# main.net
KiCad netlist of a schematic drawn in Altium Designer
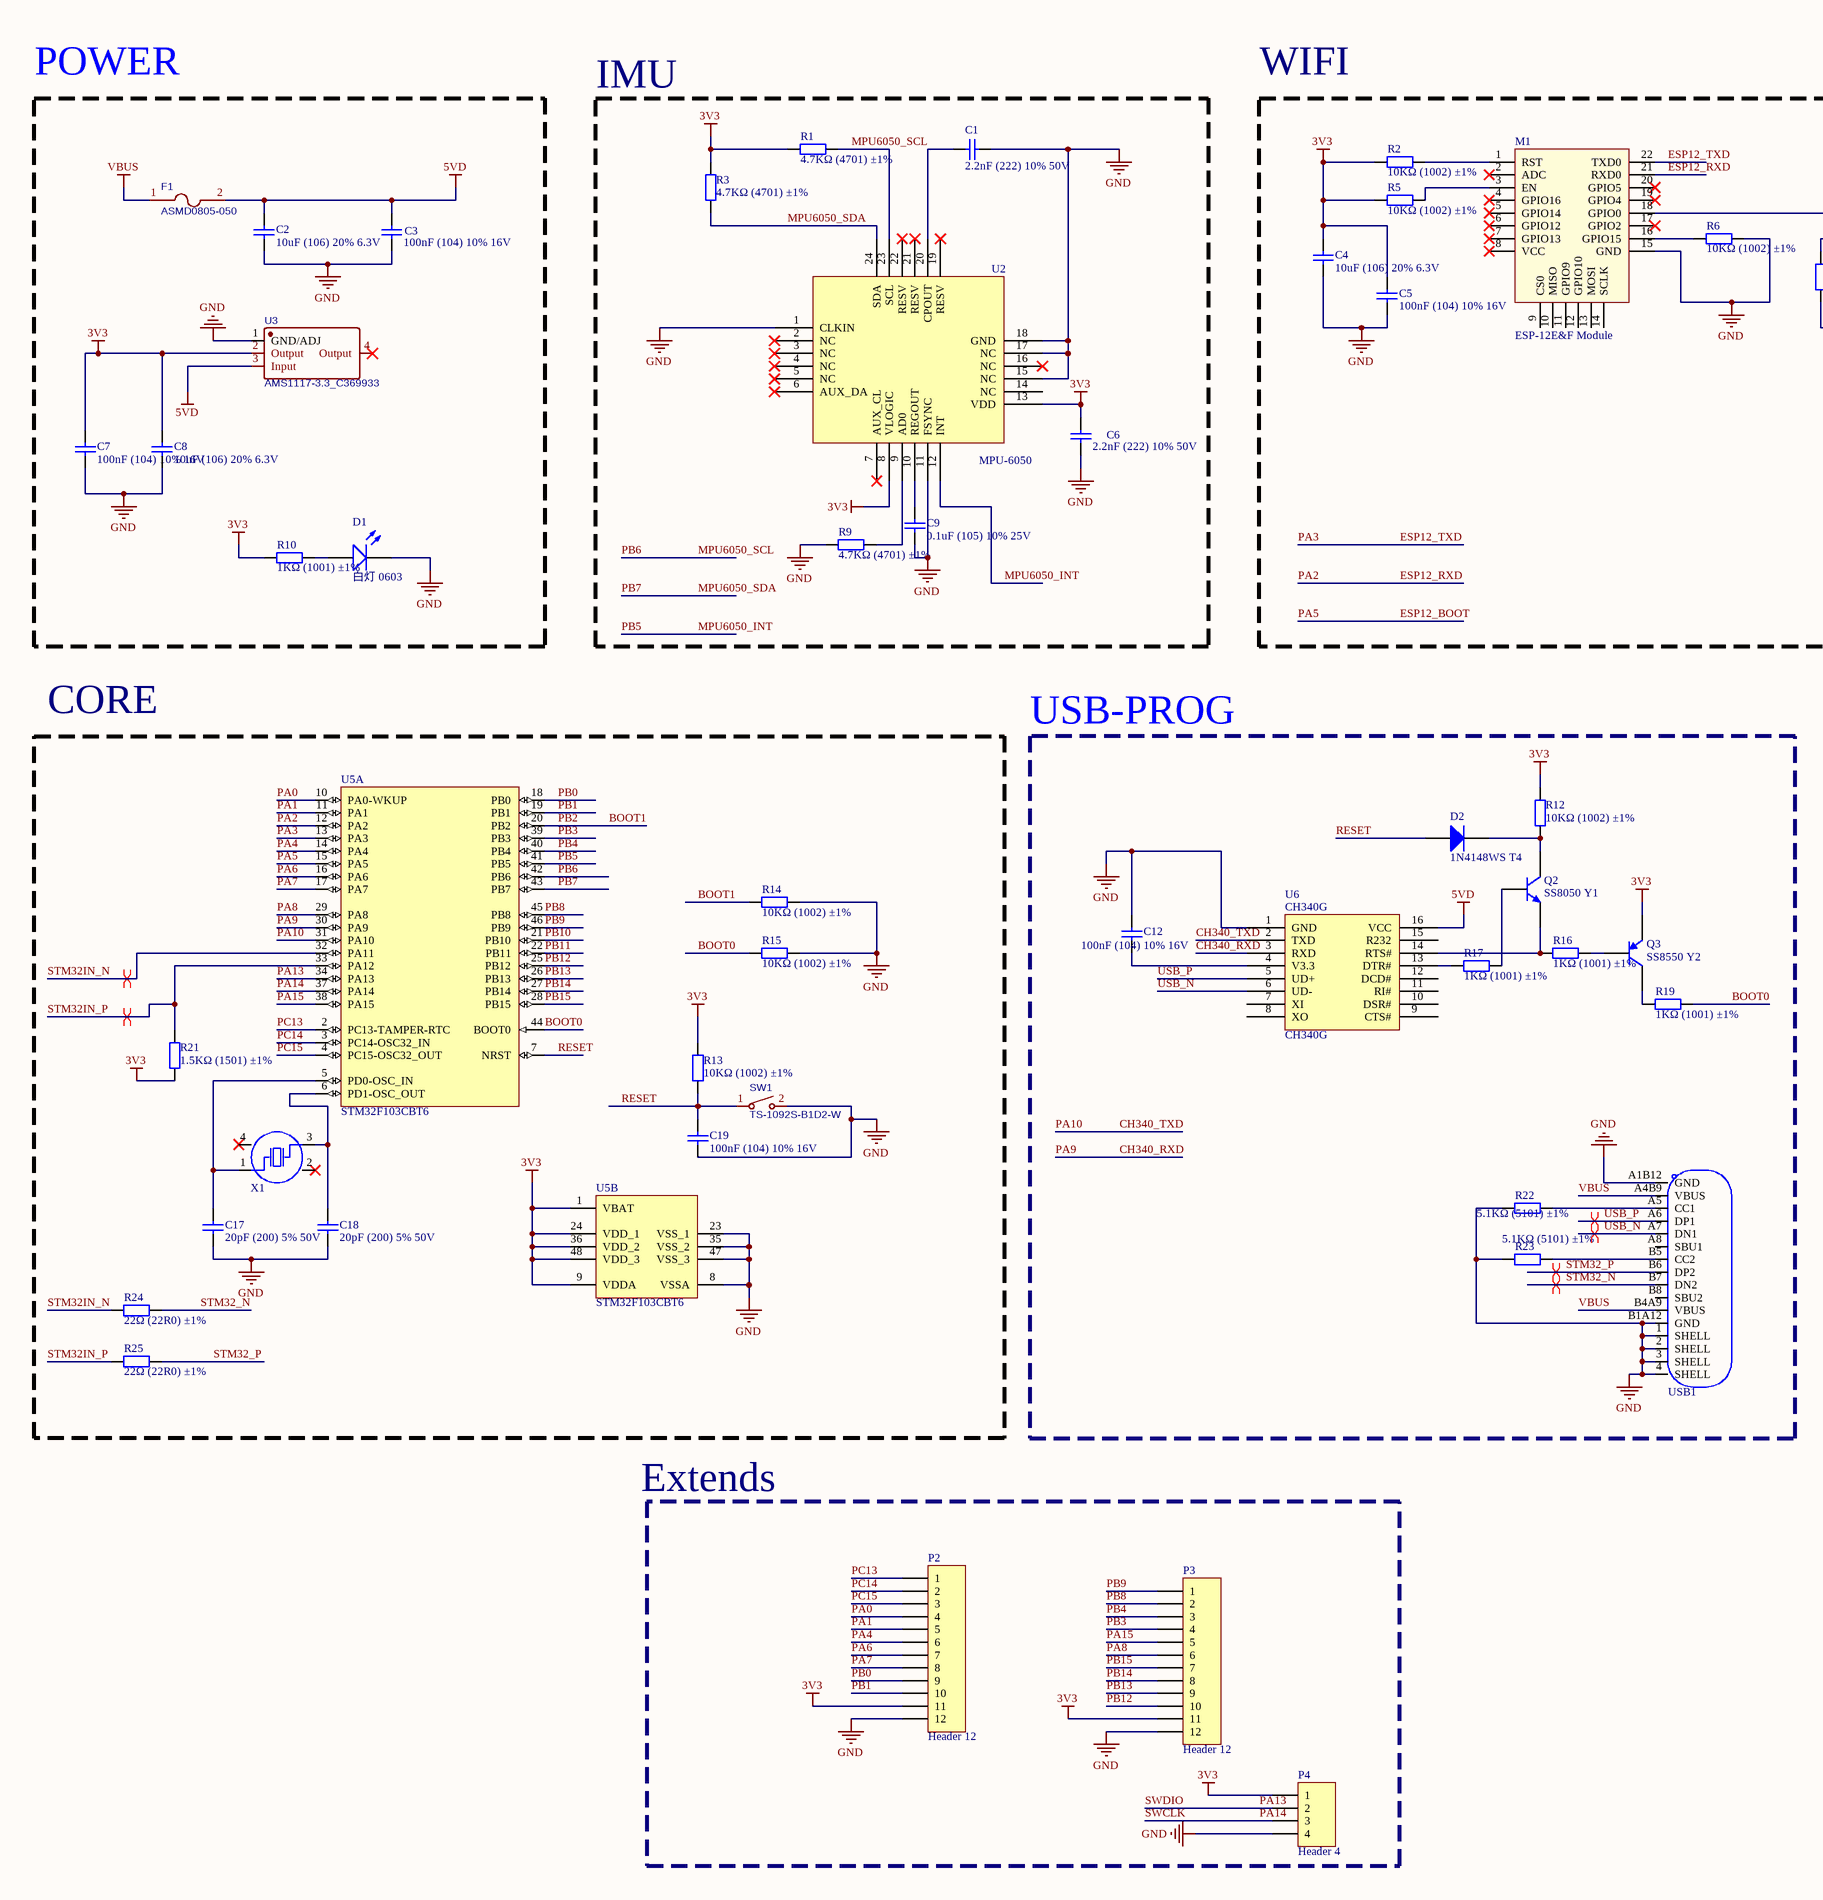
[diagram p0: main.SchDoc, left]
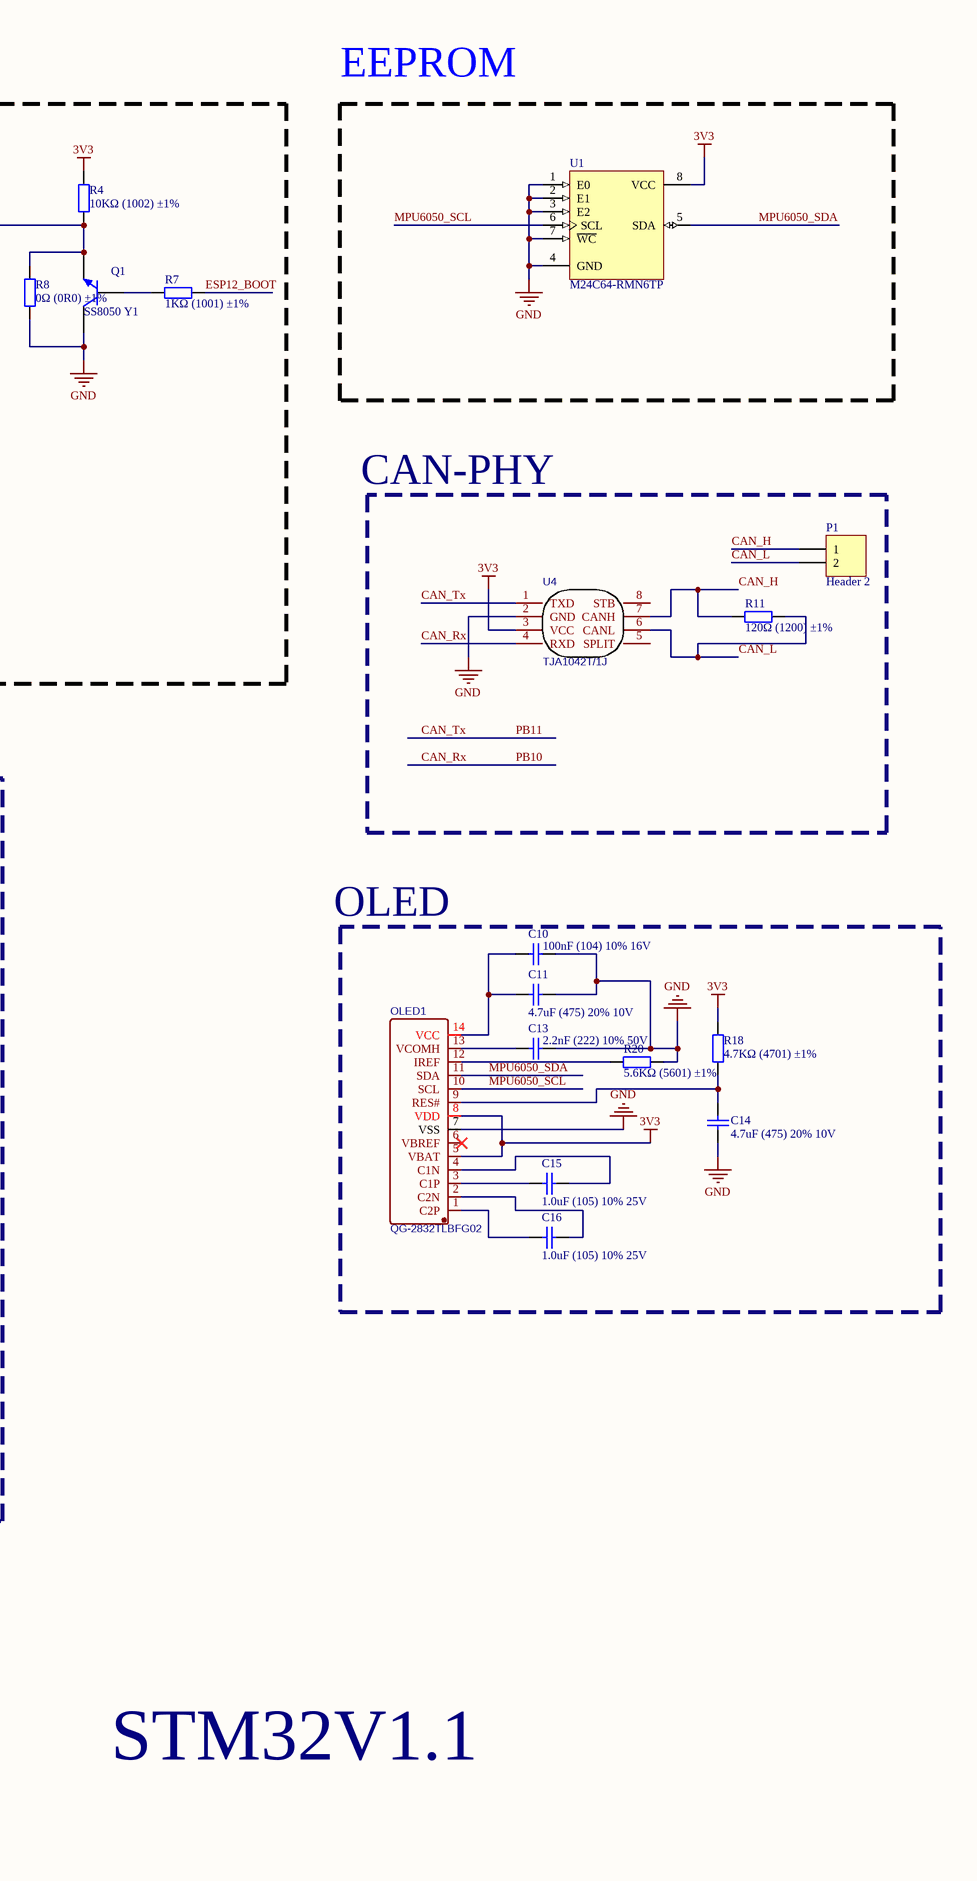
[diagram p1: main.SchDoc, right]

(export (version "E")
  (design (tool "Eeschema 10.0.6"))
  (components
    (comp (ref "C1")
      (value "2.2nF (222) 10% 50V")
      (footprint "0402_C")
      (description "贴片电容")
      (libsource (lib "Miscellaneous Devices LC") (part "0402 2.2nF (222) 10% 50V"))
    )
    (comp (ref "C2")
      (value "10uF (106) 20% 6.3V")
      (footprint "0402_C")
      (description "贴片电容")
      (libsource (lib "Cap") (part "0402 10uF (106) 20% 6.3V"))
    )
    (comp (ref "C3")
      (value "100nF (104) 10% 16V")
      (footprint "0402_C")
      (description "贴片电容")
      (libsource (lib "Cap") (part "0402 100nF (104) 10% 16V"))
    )
    (comp (ref "C4")
      (value "10uF (106) 20% 6.3V")
      (footprint "0402_C")
      (description "贴片电容")
      (libsource (lib "Miscellaneous Devices LC") (part "0402 10uF (106) 20% 6.3V"))
    )
    (comp (ref "C5")
      (value "100nF (104) 10% 16V")
      (footprint "0402_C")
      (description "贴片电容")
      (libsource (lib "Miscellaneous Devices LC") (part "0402 100nF (104) 10% 16V"))
    )
    (comp (ref "C6")
      (value "2.2nF (222) 10% 50V")
      (footprint "0402_C")
      (description "贴片电容")
      (libsource (lib "Miscellaneous Devices LC") (part "0402 2.2nF (222) 10% 50V"))
    )
    (comp (ref "C7")
      (value "100nF (104) 10% 16V")
      (footprint "0402_C")
      (description "贴片电容")
      (libsource (lib "Miscellaneous Devices LC") (part "0402 100nF (104) 10% 16V"))
    )
    (comp (ref "C8")
      (value "10uF (106) 20% 6.3V")
      (footprint "0402_C")
      (description "贴片电容")
      (libsource (lib "Miscellaneous Devices LC") (part "0402 10uF (106) 20% 6.3V"))
    )
    (comp (ref "C9")
      (value "0.1uF (105) 10% 25V")
      (footprint "0402_C")
      (description "贴片电容")
      (libsource (lib "Miscellaneous Devices LC") (part "0402 1.0uF (105) 10% 25V"))
    )
    (comp (ref "C10")
      (value "100nF (104) 10% 16V")
      (footprint "0402_C")
      (description "贴片电容")
      (libsource (lib "Miscellaneous Devices LC") (part "0402 100nF (104) 10% 16V"))
    )
    (comp (ref "C11")
      (value "4.7uF (475) 20% 10V")
      (footprint "0402_C")
      (description "贴片电容")
      (libsource (lib "Miscellaneous Devices LC") (part "0402 4.7uF (475) 20% 10V"))
    )
    (comp (ref "C12")
      (value "100nF (104) 10% 16V")
      (footprint "0402_C")
      (description "贴片电容")
      (libsource (lib "Miscellaneous Devices LC") (part "0402 100nF (104) 10% 16V"))
    )
    (comp (ref "C13")
      (value "2.2nF (222) 10% 50V")
      (footprint "0402_C")
      (description "贴片电容")
      (libsource (lib "Miscellaneous Devices LC") (part "0402 2.2nF (222) 10% 50V"))
    )
    (comp (ref "C14")
      (value "4.7uF (475) 20% 10V")
      (footprint "0402_C")
      (description "贴片电容")
      (libsource (lib "Miscellaneous Devices LC") (part "0402 4.7uF (475) 20% 10V"))
    )
    (comp (ref "C15")
      (value "1.0uF (105) 10% 25V")
      (footprint "0402_C")
      (description "贴片电容")
      (libsource (lib "Miscellaneous Devices LC") (part "0402 1.0uF (105) 10% 25V"))
    )
    (comp (ref "C16")
      (value "1.0uF (105) 10% 25V")
      (footprint "0402_C")
      (description "贴片电容")
      (libsource (lib "Miscellaneous Devices LC") (part "0402 1.0uF (105) 10% 25V"))
    )
    (comp (ref "C17")
      (value "20pF (200) 5% 50V")
      (footprint "0402_C")
      (description "贴片电容")
      (libsource (lib "Miscellaneous Devices LC") (part "0402 20pF (200) 5% 50V"))
    )
    (comp (ref "C18")
      (value "20pF (200) 5% 50V")
      (footprint "0402_C")
      (description "贴片电容")
      (libsource (lib "Miscellaneous Devices LC") (part "0402 20pF (200) 5% 50V"))
    )
    (comp (ref "C19")
      (value "100nF (104) 10% 16V")
      (footprint "0402_C")
      (description "贴片电容")
      (libsource (lib "Miscellaneous Devices LC") (part "0402 100nF (104) 10% 16V"))
    )
    (comp (ref "D1")
      (value "白灯 0603")
      (footprint "0603_LED_S1")
      (description "发光二极管")
      (libsource (lib "Miscellaneous Devices LC") (part "0603 白灯"))
    )
    (comp (ref "D2")
      (value "1N4148WS T4")
      (footprint "SOD-323_L1.8-W1.3-LS2.5-RD")
      (description "二极管")
      (libsource (lib "Miscellaneous Devices LC") (part "SOD-323 1N4148WS T4"))
    )
    (comp (ref "F1")
      (value "ASMD0805-050")
      (footprint "ASMD0805")
      (fields (field (name "BOM_SUPPLIER PART") "C135329") (field (name "CONTRIBUTOR") "LCSC"))
      (libsource (lib "mysch") (part "ASMD0805-050"))
    )
    (comp (ref "M1")
      (value "ESP-12E&F Module")
      (footprint "ESP-12E&F Module")
      (libsource (lib "smartclock") (part "ESP-12E&F Module"))
    )
    (comp (ref "OLED1")
      (value "QG-2832TLBFG02")
      (footprint "OLED-SMD_QG-9616TSWCG02")
      (fields (field (name "BOM_SUPPLIER PART") "C91220") (field (name "CONTRIBUTOR") "LCSC"))
      (libsource (lib "mysch") (part "OLED"))
    )
    (comp (ref "P1")
      (value "Header 2")
      (footprint "HDR1X2")
      (description "Header, 2-Pin")
      (fields (field (name "PUBLISHER") "Altium Limited"))
      (libsource (lib "Miscellaneous Connectors") (part "Header 2"))
    )
    (comp (ref "P2")
      (value "Header 12")
      (footprint "HDR1X12")
      (description "Header, 12-Pin")
      (fields (field (name "PUBLISHER") "Altium Limited"))
      (libsource (lib "Miscellaneous Connectors") (part "Header 12"))
    )
    (comp (ref "P3")
      (value "Header 12")
      (footprint "HDR1X12")
      (description "Header, 12-Pin")
      (fields (field (name "PUBLISHER") "Altium Limited"))
      (libsource (lib "Miscellaneous Connectors") (part "Header 12"))
    )
    (comp (ref "P4")
      (value "Header 4")
      (footprint "HDR1X4")
      (description "Header, 4-Pin")
      (fields (field (name "PUBLISHER") "Altium Limited"))
      (libsource (lib "Miscellaneous Connectors") (part "Header 4"))
    )
    (comp (ref "Q1")
      (value "SS8050 Y1")
      (footprint "SOT-23(SOT-23-3)")
      (description "三极管")
      (libsource (lib "Miscellaneous Devices LC") (part "SOT-23 SS8050 Y1"))
    )
    (comp (ref "Q2")
      (value "SS8050 Y1")
      (footprint "SOT-23(SOT-23-3)")
      (description "三极管")
      (libsource (lib "Miscellaneous Devices LC") (part "SOT-23 SS8050 Y1"))
    )
    (comp (ref "Q3")
      (value "SS8550 Y2")
      (footprint "SOT-23(SOT-23-3)")
      (description "三极管")
      (libsource (lib "Miscellaneous Devices LC") (part "SOT-23 SS8550 Y2"))
    )
    (comp (ref "R1")
      (value "4.7KΩ (4701) ±1%")
      (footprint "0402_R")
      (description "贴片电阻")
      (libsource (lib "") (part "0402 4.7KΩ (4701) 1%_2"))
    )
    (comp (ref "R2")
      (value "10KΩ (1002) ±1%")
      (footprint "0402_R")
      (description "贴片电阻")
      (libsource (lib "Miscellaneous Devices LC") (part "0402 10KΩ (1002) 1%"))
    )
    (comp (ref "R3")
      (value "4.7KΩ (4701) ±1%")
      (footprint "0402_R")
      (description "贴片电阻")
      (libsource (lib "Miscellaneous Devices LC") (part "0402 4.7KΩ (4701) 1%"))
    )
    (comp (ref "R4")
      (value "10KΩ (1002) ±1%")
      (footprint "0402_R")
      (description "贴片电阻")
      (libsource (lib "") (part "0402 10KΩ (1002) 1%_1"))
    )
    (comp (ref "R5")
      (value "10KΩ (1002) ±1%")
      (footprint "0402_R")
      (description "贴片电阻")
      (libsource (lib "Miscellaneous Devices LC") (part "0402 10KΩ (1002) 1%"))
    )
    (comp (ref "R6")
      (value "10KΩ (1002) ±1%")
      (footprint "0402_R")
      (description "贴片电阻")
      (libsource (lib "Miscellaneous Devices LC") (part "0402 10KΩ (1002) 1%"))
    )
    (comp (ref "R7")
      (value "1KΩ (1001) ±1%")
      (footprint "0402_R")
      (description "贴片电阻")
      (libsource (lib "Miscellaneous Devices LC") (part "0402 1KΩ (1001) 1%"))
    )
    (comp (ref "R8")
      (value "0Ω (0R0) ±1%")
      (footprint "0402_R")
      (description "贴片电阻")
      (libsource (lib "Miscellaneous Devices LC") (part "0402 0Ω (0R0) 1%"))
    )
    (comp (ref "R9")
      (value "4.7KΩ (4701) ±1%")
      (footprint "0402_R")
      (description "贴片电阻")
      (libsource (lib "") (part "0402 4.7KΩ (4701) 1%_1"))
    )
    (comp (ref "R10")
      (value "1KΩ (1001) ±1%")
      (footprint "0402_R")
      (description "贴片电阻")
      (libsource (lib "RES") (part "0402 1KΩ (1001) 1%"))
    )
    (comp (ref "R11")
      (value "120Ω (1200) ±1%")
      (footprint "0402_R")
      (description "贴片电阻")
      (libsource (lib "Miscellaneous Devices LC") (part "0402 120Ω (1200) 1%"))
    )
    (comp (ref "R12")
      (value "10KΩ (1002) ±1%")
      (footprint "0402_R")
      (description "贴片电阻")
      (libsource (lib "") (part "0402 10KΩ (1002) 1%_1"))
    )
    (comp (ref "R13")
      (value "10KΩ (1002) ±1%")
      (footprint "0402_R")
      (description "贴片电阻")
      (libsource (lib "") (part "0402 10KΩ (1002) 1%_1"))
    )
    (comp (ref "R14")
      (value "10KΩ (1002) ±1%")
      (footprint "0402_R")
      (description "贴片电阻")
      (libsource (lib "Miscellaneous Devices LC") (part "0402 10KΩ (1002) 1%"))
    )
    (comp (ref "R15")
      (value "10KΩ (1002) ±1%")
      (footprint "0402_R")
      (description "贴片电阻")
      (libsource (lib "Miscellaneous Devices LC") (part "0402 10KΩ (1002) 1%"))
    )
    (comp (ref "R16")
      (value "1KΩ (1001) ±1%")
      (footprint "0402_R")
      (description "贴片电阻")
      (libsource (lib "Miscellaneous Devices LC") (part "0402 1KΩ (1001) 1%"))
    )
    (comp (ref "R17")
      (value "1KΩ (1001) ±1%")
      (footprint "0402_R")
      (description "贴片电阻")
      (libsource (lib "Miscellaneous Devices LC") (part "0402 1KΩ (1001) 1%"))
    )
    (comp (ref "R18")
      (value "4.7KΩ (4701) ±1%")
      (footprint "0402_R")
      (description "贴片电阻")
      (libsource (lib "Miscellaneous Devices LC") (part "0402 4.7KΩ (4701) 1%"))
    )
    (comp (ref "R19")
      (value "1KΩ (1001) ±1%")
      (footprint "0402_R")
      (description "贴片电阻")
      (libsource (lib "") (part "0402 1KΩ (1001) 1%_1"))
    )
    (comp (ref "R20")
      (value "5.6KΩ (5601) ±1%")
      (footprint "0402_R")
      (description "贴片电阻")
      (libsource (lib "Miscellaneous Devices LC") (part "0402 5.6KΩ (5601) 1%"))
    )
    (comp (ref "R21")
      (value "1.5KΩ (1501) ±1%")
      (footprint "0402_R")
      (description "贴片电阻")
      (libsource (lib "Miscellaneous Devices LC") (part "0402 1.5KΩ (1501) 1%"))
    )
    (comp (ref "R22")
      (value "5.1KΩ (5101) ±1%")
      (footprint "0402_R")
      (description "贴片电阻")
      (libsource (lib "RES") (part "0402 5.1KΩ (5101) 1%"))
    )
    (comp (ref "R23")
      (value "5.1KΩ (5101) ±1%")
      (footprint "0402_R")
      (description "贴片电阻")
      (libsource (lib "RES") (part "0402 5.1KΩ (5101) 1%"))
    )
    (comp (ref "R24")
      (value "22Ω (22R0) ±1%")
      (footprint "0402_R")
      (description "贴片电阻")
      (libsource (lib "Miscellaneous Devices LC") (part "0402 22Ω (22R0) 1%"))
    )
    (comp (ref "R25")
      (value "22Ω (22R0) ±1%")
      (footprint "0402_R")
      (description "贴片电阻")
      (libsource (lib "Miscellaneous Devices LC") (part "0402 22Ω (22R0) 1%"))
    )
    (comp (ref "SW1")
      (value "TS-1092S-B1D2-W")
      (footprint "SW-SMD_L6.1-W3.6-LS7.9")
      (description "触控开关")
      (fields (field (name "BOM_SUPPLIER PART") "C782859") (field (name "CONTRIBUTOR") "LCSC"))
      (libsource (lib "mysch") (part "TS-1092S-B1D2-W"))
    )
    (comp (ref "U1")
      (value "M24C64-RMN6TP")
      (footprint "SOIC-8_150mil")
      (description "EEPROM")
      (libsource (lib "Miscellaneous Devices LC") (part "M24C64-RMN6TP"))
    )
    (comp (ref "U2")
      (value "MPU-6050")
      (footprint "QFN-24_4x4x05P")
      (description "传感器")
      (libsource (lib "Miscellaneous Devices LC") (part "MPU-6050"))
    )
    (comp (ref "U3")
      (value "AMS1117-3.3_C369933")
      (footprint "SOT-223-AMS1117")
      (fields
        (field (name "BOM_SUPPLIER PART") "C369933")
        (field (name "BOM_MANUFACTURER PART") "AMS1117-3.3")
        (field (name "CONTRIBUTOR") "LCSC")
      )
      (libsource (lib "mysch") (part "AMS1117-3.3"))
    )
    (comp (ref "U4")
      (value "TJA1042T/1J")
      (footprint "SOIC-8_L5.0-W4.0-P1.27-LS6.0-BL")
      (description "CAN芯片")
      (fields (field (name "BOM_SUPPLIER PART") "C53670"))
      (libsource (lib "mysch") (part "TJA1042T/1J"))
    )
    (comp (ref "U5")
      (value "STM32F103CBT6")
      (footprint "STM-LQFP48_N")
      (libsource (lib "STMicroelectronics STM32 F1") (part "STM32F103CBT6"))
    )
    (comp (ref "U6")
      (value "CH340G")
      (footprint "SOIC-16_150mil")
      (description "USB")
      (libsource (lib "Miscellaneous Devices LC") (part "CH340G_[C14267]"))
    )
    (comp (ref "USB1")
      (value "TYPE-C16PIN")
      (footprint "TYPE-C-SMD")
      (fields (field (name "MANUFACTURER") "SHOU HAN(首韩)"))
      (libsource (lib "mysch") (part "TYPE-C16PIN"))
    )
    (comp (ref "X1")
      (value "8MHZ")
      (footprint "OSC-SMD_4P-L5.0-W3.2-BL")
      (description "8M 30PPM 20pf")
      (fields
        (field (name "MANUFACTURER") "SIWARD(台湾希华)")
        (field (name "MANUFACTURER PART") "XTL541200-C282-030")
      )
      (libsource (lib "mysch") (part "8MHZ"))
    )
  )
  (nets
    (net (code "1") (name "/BOOT0") (class "Default")
      (node (ref "R15") (pin "1") (pinfunction "1_1") (pintype "passive"))
      (node (ref "R19") (pin "1") (pinfunction "1_1") (pintype "passive"))
      (node (ref "U5") (pin "44") (pinfunction "BOOT0_44") (pintype "input"))
    )
    (net (code "2") (name "/BOOT1") (class "Default")
      (node (ref "R14") (pin "1") (pinfunction "1_1") (pintype "passive"))
      (node (ref "U5") (pin "20") (pinfunction "PB2_20") (pintype "bidirectional"))
    )
    (net (code "3") (name "/CAN_H") (class "Default")
      (node (ref "P1") (pin "1") (pinfunction "1_1") (pintype "passive"))
      (node (ref "R11") (pin "1") (pinfunction "1_1") (pintype "passive"))
      (node (ref "U4") (pin "7") (pinfunction "CANH_7") (pintype "passive"))
    )
    (net (code "4") (name "/CAN_L") (class "Default")
      (node (ref "P1") (pin "2") (pinfunction "2_2") (pintype "passive"))
      (node (ref "R11") (pin "2") (pinfunction "2_2") (pintype "passive"))
      (node (ref "U4") (pin "6") (pinfunction "CANL_6") (pintype "passive"))
    )
    (net (code "5") (name "/CAN_Rx") (class "Default")
      (node (ref "U4") (pin "4") (pinfunction "RXD_4") (pintype "passive"))
      (node (ref "U5") (pin "21") (pinfunction "PB10_21") (pintype "bidirectional"))
    )
    (net (code "6") (name "/CAN_Tx") (class "Default")
      (node (ref "U4") (pin "1") (pinfunction "TXD_1") (pintype "passive"))
      (node (ref "U5") (pin "22") (pinfunction "PB11_22") (pintype "bidirectional"))
    )
    (net (code "7") (name "/CH340_RXD") (class "Default")
      (node (ref "U5") (pin "30") (pinfunction "PA9_30") (pintype "bidirectional"))
      (node (ref "U6") (pin "3") (pinfunction "RXD_3") (pintype "passive"))
    )
    (net (code "8") (name "/CH340_TXD") (class "Default")
      (node (ref "U5") (pin "31") (pinfunction "PA10_31") (pintype "bidirectional"))
      (node (ref "U6") (pin "2") (pinfunction "TXD_2") (pintype "passive"))
    )
    (net (code "9") (name "/ESP12_BOOT") (class "Default")
      (node (ref "R7") (pin "2") (pinfunction "2_2") (pintype "passive"))
      (node (ref "U5") (pin "15") (pinfunction "PA5_15") (pintype "bidirectional"))
    )
    (net (code "10") (name "/ESP12_RXD") (class "Default")
      (node (ref "M1") (pin "21") (pinfunction "RXD0_21") (pintype "passive"))
      (node (ref "U5") (pin "12") (pinfunction "PA2_12") (pintype "bidirectional"))
    )
    (net (code "11") (name "/ESP12_TXD") (class "Default")
      (node (ref "M1") (pin "22") (pinfunction "TXD0_22") (pintype "passive"))
      (node (ref "U5") (pin "13") (pinfunction "PA3_13") (pintype "bidirectional"))
    )
    (net (code "12") (name "/MPU6050_INT") (class "Default")
      (node (ref "U2") (pin "12") (pinfunction "INT_12") (pintype "passive"))
      (node (ref "U5") (pin "41") (pinfunction "PB5_41") (pintype "bidirectional"))
    )
    (net (code "13") (name "/MPU6050_SCL") (class "Default")
      (node (ref "OLED1") (pin "10") (pinfunction "SCL_10") (pintype "passive"))
      (node (ref "R1") (pin "2") (pinfunction "2_2") (pintype "passive"))
      (node (ref "U1") (pin "6") (pinfunction "SCL_6") (pintype "input"))
      (node (ref "U2") (pin "23") (pinfunction "SCL_23") (pintype "passive"))
      (node (ref "U5") (pin "42") (pinfunction "PB6_42") (pintype "bidirectional"))
    )
    (net (code "14") (name "/MPU6050_SDA") (class "Default")
      (node (ref "OLED1") (pin "11") (pinfunction "SDA_11") (pintype "passive"))
      (node (ref "R3") (pin "1") (pinfunction "1_1") (pintype "passive"))
      (node (ref "U1") (pin "5") (pinfunction "SDA_5") (pintype "bidirectional"))
      (node (ref "U2") (pin "24") (pinfunction "SDA_24") (pintype "passive"))
      (node (ref "U5") (pin "43") (pinfunction "PB7_43") (pintype "bidirectional"))
    )
    (net (code "15") (name "/PA0") (class "Default")
      (node (ref "P2") (pin "4") (pinfunction "4_4") (pintype "passive"))
      (node (ref "U5") (pin "10") (pinfunction "PA0-WKUP_10") (pintype "bidirectional"))
    )
    (net (code "16") (name "/PA1") (class "Default")
      (node (ref "P2") (pin "5") (pinfunction "5_5") (pintype "passive"))
      (node (ref "U5") (pin "11") (pinfunction "PA1_11") (pintype "bidirectional"))
    )
    (net (code "17") (name "/PA4") (class "Default")
      (node (ref "P2") (pin "6") (pinfunction "6_6") (pintype "passive"))
      (node (ref "U5") (pin "14") (pinfunction "PA4_14") (pintype "bidirectional"))
    )
    (net (code "18") (name "/PA6") (class "Default")
      (node (ref "P2") (pin "7") (pinfunction "7_7") (pintype "passive"))
      (node (ref "U5") (pin "16") (pinfunction "PA6_16") (pintype "bidirectional"))
    )
    (net (code "19") (name "/PA7") (class "Default")
      (node (ref "P2") (pin "8") (pinfunction "8_8") (pintype "passive"))
      (node (ref "U5") (pin "17") (pinfunction "PA7_17") (pintype "bidirectional"))
    )
    (net (code "20") (name "/PA8") (class "Default")
      (node (ref "P3") (pin "6") (pinfunction "6_6") (pintype "passive"))
      (node (ref "U5") (pin "29") (pinfunction "PA8_29") (pintype "bidirectional"))
    )
    (net (code "21") (name "/PA13") (class "Default")
      (node (ref "P4") (pin "2") (pinfunction "2_2") (pintype "passive"))
      (node (ref "U5") (pin "34") (pinfunction "PA13_34") (pintype "bidirectional"))
    )
    (net (code "22") (name "/PA14") (class "Default")
      (node (ref "P4") (pin "3") (pinfunction "3_3") (pintype "passive"))
      (node (ref "U5") (pin "37") (pinfunction "PA14_37") (pintype "bidirectional"))
    )
    (net (code "23") (name "/PA15") (class "Default")
      (node (ref "P3") (pin "5") (pinfunction "5_5") (pintype "passive"))
      (node (ref "U5") (pin "38") (pinfunction "PA15_38") (pintype "bidirectional"))
    )
    (net (code "24") (name "/PB0") (class "Default")
      (node (ref "P2") (pin "9") (pinfunction "9_9") (pintype "passive"))
      (node (ref "U5") (pin "18") (pinfunction "PB0_18") (pintype "bidirectional"))
    )
    (net (code "25") (name "/PB1") (class "Default")
      (node (ref "P2") (pin "10") (pinfunction "10_10") (pintype "passive"))
      (node (ref "U5") (pin "19") (pinfunction "PB1_19") (pintype "bidirectional"))
    )
    (net (code "26") (name "/PB3") (class "Default")
      (node (ref "P3") (pin "4") (pinfunction "4_4") (pintype "passive"))
      (node (ref "U5") (pin "39") (pinfunction "PB3_39") (pintype "bidirectional"))
    )
    (net (code "27") (name "/PB4") (class "Default")
      (node (ref "P3") (pin "3") (pinfunction "3_3") (pintype "passive"))
      (node (ref "U5") (pin "40") (pinfunction "PB4_40") (pintype "bidirectional"))
    )
    (net (code "28") (name "/PB8") (class "Default")
      (node (ref "P3") (pin "2") (pinfunction "2_2") (pintype "passive"))
      (node (ref "U5") (pin "45") (pinfunction "PB8_45") (pintype "bidirectional"))
    )
    (net (code "29") (name "/PB9") (class "Default")
      (node (ref "P3") (pin "1") (pinfunction "1_1") (pintype "passive"))
      (node (ref "U5") (pin "46") (pinfunction "PB9_46") (pintype "bidirectional"))
    )
    (net (code "30") (name "/PB12") (class "Default")
      (node (ref "P3") (pin "10") (pinfunction "10_10") (pintype "passive"))
      (node (ref "U5") (pin "25") (pinfunction "PB12_25") (pintype "bidirectional"))
    )
    (net (code "31") (name "/PB13") (class "Default")
      (node (ref "P3") (pin "9") (pinfunction "9_9") (pintype "passive"))
      (node (ref "U5") (pin "26") (pinfunction "PB13_26") (pintype "bidirectional"))
    )
    (net (code "32") (name "/PB14") (class "Default")
      (node (ref "P3") (pin "8") (pinfunction "8_8") (pintype "passive"))
      (node (ref "U5") (pin "27") (pinfunction "PB14_27") (pintype "bidirectional"))
    )
    (net (code "33") (name "/PB15") (class "Default")
      (node (ref "P3") (pin "7") (pinfunction "7_7") (pintype "passive"))
      (node (ref "U5") (pin "28") (pinfunction "PB15_28") (pintype "bidirectional"))
    )
    (net (code "34") (name "/PC13") (class "Default")
      (node (ref "P2") (pin "1") (pinfunction "1_1") (pintype "passive"))
      (node (ref "U5") (pin "2") (pinfunction "PC13-TAMPER-RTC_2") (pintype "bidirectional"))
    )
    (net (code "35") (name "/PC14") (class "Default")
      (node (ref "P2") (pin "2") (pinfunction "2_2") (pintype "passive"))
      (node (ref "U5") (pin "3") (pinfunction "PC14-OSC32_IN_3") (pintype "bidirectional"))
    )
    (net (code "36") (name "/PC15") (class "Default")
      (node (ref "P2") (pin "3") (pinfunction "3_3") (pintype "passive"))
      (node (ref "U5") (pin "4") (pinfunction "PC15-OSC32_OUT_4") (pintype "bidirectional"))
    )
    (net (code "37") (name "/RESET") (class "Default")
      (node (ref "C19") (pin "2") (pinfunction "2_2") (pintype "passive"))
      (node (ref "D2") (pin "1") (pinfunction "A_1") (pintype "passive"))
      (node (ref "R13") (pin "1") (pinfunction "1_1") (pintype "passive"))
      (node (ref "SW1") (pin "1") (pinfunction "1_1") (pintype "passive"))
      (node (ref "U5") (pin "7") (pinfunction "NRST_7") (pintype "bidirectional"))
    )
    (net (code "38") (name "/STM32IN_N") (class "Default")
      (node (ref "R24") (pin "1") (pinfunction "1_1") (pintype "passive"))
      (node (ref "U5") (pin "32") (pinfunction "PA11_32") (pintype "bidirectional"))
    )
    (net (code "39") (name "/STM32IN_P") (class "Default")
      (node (ref "R21") (pin "2") (pinfunction "2_2") (pintype "passive"))
      (node (ref "R25") (pin "1") (pinfunction "1_1") (pintype "passive"))
      (node (ref "U5") (pin "33") (pinfunction "PA12_33") (pintype "bidirectional"))
    )
    (net (code "40") (name "/STM32_N") (class "Default")
      (node (ref "R24") (pin "2") (pinfunction "2_2") (pintype "passive"))
      (node (ref "USB1") (pin "B7") (pinfunction "DN2_B7") (pintype "passive"))
    )
    (net (code "41") (name "/STM32_P") (class "Default")
      (node (ref "R25") (pin "2") (pinfunction "2_2") (pintype "passive"))
      (node (ref "USB1") (pin "B6") (pinfunction "DP2_B6") (pintype "passive"))
    )
    (net (code "42") (name "/USB_N") (class "Default")
      (node (ref "U6") (pin "6") (pinfunction "UD-_6") (pintype "passive"))
      (node (ref "USB1") (pin "A7") (pinfunction "DN1_A7") (pintype "passive"))
    )
    (net (code "43") (name "/USB_P") (class "Default")
      (node (ref "U6") (pin "5") (pinfunction "UD+_5") (pintype "passive"))
      (node (ref "USB1") (pin "A6") (pinfunction "DP1_A6") (pintype "passive"))
    )
    (net (code "44") (name "3V3") (class "Default")
      (node (ref "C4") (pin "2") (pinfunction "2_2") (pintype "passive"))
      (node (ref "C5") (pin "2") (pinfunction "2_2") (pintype "passive"))
      (node (ref "C6") (pin "2") (pinfunction "2_2") (pintype "passive"))
      (node (ref "C7") (pin "2") (pinfunction "2_2") (pintype "passive"))
      (node (ref "C8") (pin "2") (pinfunction "2_2") (pintype "passive"))
      (node (ref "OLED1") (pin "5") (pinfunction "VBAT_5") (pintype "passive"))
      (node (ref "OLED1") (pin "8") (pinfunction "VDD_8") (pintype "passive"))
      (node (ref "P2") (pin "11") (pinfunction "11_11") (pintype "passive"))
      (node (ref "P3") (pin "11") (pinfunction "11_11") (pintype "passive"))
      (node (ref "P4") (pin "1") (pinfunction "1_1") (pintype "passive"))
      (node (ref "Q3") (pin "2") (pinfunction "E_2") (pintype "passive"))
      (node (ref "R1") (pin "1") (pinfunction "1_1") (pintype "passive"))
      (node (ref "R10") (pin "1") (pinfunction "1_1") (pintype "passive"))
      (node (ref "R12") (pin "2") (pinfunction "2_2") (pintype "passive"))
      (node (ref "R13") (pin "2") (pinfunction "2_2") (pintype "passive"))
      (node (ref "R18") (pin "2") (pinfunction "2_2") (pintype "passive"))
      (node (ref "R2") (pin "1") (pinfunction "1_1") (pintype "passive"))
      (node (ref "R21") (pin "1") (pinfunction "1_1") (pintype "passive"))
      (node (ref "R3") (pin "2") (pinfunction "2_2") (pintype "passive"))
      (node (ref "R4") (pin "2") (pinfunction "2_2") (pintype "passive"))
      (node (ref "R5") (pin "1") (pinfunction "1_1") (pintype "passive"))
      (node (ref "U1") (pin "8") (pinfunction "VCC_8") (pintype "power_in"))
      (node (ref "U2") (pin "13") (pinfunction "VDD_13") (pintype "passive"))
      (node (ref "U2") (pin "8") (pinfunction "VLOGIC_8") (pintype "passive"))
      (node (ref "U3") (pin "2") (pinfunction "Output_2") (pintype "passive"))
      (node (ref "U4") (pin "3") (pinfunction "VCC_3") (pintype "passive"))
      (node (ref "U5") (pin "1") (pinfunction "VBAT_1") (pintype "power_in"))
      (node (ref "U5") (pin "24") (pinfunction "VDD_1_24") (pintype "power_in"))
      (node (ref "U5") (pin "36") (pinfunction "VDD_2_36") (pintype "power_in"))
      (node (ref "U5") (pin "48") (pinfunction "VDD_3_48") (pintype "power_in"))
      (node (ref "U5") (pin "9") (pinfunction "VDDA_9") (pintype "power_in"))
    )
    (net (code "45") (name "5VD") (class "Default")
      (node (ref "C2") (pin "2") (pinfunction "2_2") (pintype "passive"))
      (node (ref "C3") (pin "2") (pinfunction "2_2") (pintype "passive"))
      (node (ref "F1") (pin "2") (pinfunction "2_2") (pintype "passive"))
      (node (ref "U3") (pin "3") (pinfunction "Input_3") (pintype "passive"))
      (node (ref "U6") (pin "16") (pinfunction "VCC_16") (pintype "passive"))
    )
    (net (code "46") (name "GND") (class "Default")
      (node (ref "C1") (pin "2") (pinfunction "2_2") (pintype "passive"))
      (node (ref "C10") (pin "2") (pinfunction "2_2") (pintype "passive"))
      (node (ref "C11") (pin "2") (pinfunction "2_2") (pintype "passive"))
      (node (ref "C12") (pin "2") (pinfunction "2_2") (pintype "passive"))
      (node (ref "C13") (pin "1") (pinfunction "1_1") (pintype "passive"))
      (node (ref "C14") (pin "1") (pinfunction "1_1") (pintype "passive"))
      (node (ref "C17") (pin "1") (pinfunction "1_1") (pintype "passive"))
      (node (ref "C18") (pin "1") (pinfunction "1_1") (pintype "passive"))
      (node (ref "C19") (pin "1") (pinfunction "1_1") (pintype "passive"))
      (node (ref "C2") (pin "1") (pinfunction "1_1") (pintype "passive"))
      (node (ref "C3") (pin "1") (pinfunction "1_1") (pintype "passive"))
      (node (ref "C4") (pin "1") (pinfunction "1_1") (pintype "passive"))
      (node (ref "C5") (pin "1") (pinfunction "1_1") (pintype "passive"))
      (node (ref "C6") (pin "1") (pinfunction "1_1") (pintype "passive"))
      (node (ref "C7") (pin "1") (pinfunction "1_1") (pintype "passive"))
      (node (ref "C8") (pin "1") (pinfunction "1_1") (pintype "passive"))
      (node (ref "C9") (pin "1") (pinfunction "1_1") (pintype "passive"))
      (node (ref "D1") (pin "K") (pinfunction "K_K") (pintype "passive"))
      (node (ref "M1") (pin "15") (pinfunction "GND_15") (pintype "passive"))
      (node (ref "OLED1") (pin "7") (pinfunction "VSS_7") (pintype "passive"))
      (node (ref "P2") (pin "12") (pinfunction "12_12") (pintype "passive"))
      (node (ref "P3") (pin "12") (pinfunction "12_12") (pintype "passive"))
      (node (ref "P4") (pin "4") (pinfunction "4_4") (pintype "passive"))
      (node (ref "Q1") (pin "3") (pinfunction "C_3") (pintype "passive"))
      (node (ref "R14") (pin "2") (pinfunction "2_2") (pintype "passive"))
      (node (ref "R15") (pin "2") (pinfunction "2_2") (pintype "passive"))
      (node (ref "R20") (pin "2") (pinfunction "2_2") (pintype "passive"))
      (node (ref "R22") (pin "1") (pinfunction "1_1") (pintype "passive"))
      (node (ref "R23") (pin "1") (pinfunction "1_1") (pintype "passive"))
      (node (ref "R6") (pin "2") (pinfunction "2_2") (pintype "passive"))
      (node (ref "R8") (pin "1") (pinfunction "1_1") (pintype "passive"))
      (node (ref "R9") (pin "2") (pinfunction "2_2") (pintype "passive"))
      (node (ref "SW1") (pin "2") (pinfunction "2_2") (pintype "passive"))
      (node (ref "U1") (pin "1") (pinfunction "E0_1") (pintype "input"))
      (node (ref "U1") (pin "2") (pinfunction "E1_2") (pintype "input"))
      (node (ref "U1") (pin "3") (pinfunction "E2_3") (pintype "input"))
      (node (ref "U1") (pin "4") (pinfunction "GND_4") (pintype "power_in"))
      (node (ref "U1") (pin "7") (pinfunction "~{WC}_7") (pintype "input"))
      (node (ref "U2") (pin "1") (pinfunction "CLKIN_1") (pintype "passive"))
      (node (ref "U2") (pin "11") (pinfunction "FSYNC_11") (pintype "passive"))
      (node (ref "U2") (pin "15") (pinfunction "NC_15") (pintype "passive"))
      (node (ref "U2") (pin "17") (pinfunction "NC_17") (pintype "passive"))
      (node (ref "U2") (pin "18") (pinfunction "GND_18") (pintype "passive"))
      (node (ref "U3") (pin "1") (pinfunction "GND/ADJ_1") (pintype "passive"))
      (node (ref "U4") (pin "2") (pinfunction "GND_2") (pintype "passive"))
      (node (ref "U5") (pin "23") (pinfunction "VSS_1_23") (pintype "power_in"))
      (node (ref "U5") (pin "35") (pinfunction "VSS_2_35") (pintype "power_in"))
      (node (ref "U5") (pin "47") (pinfunction "VSS_3_47") (pintype "power_in"))
      (node (ref "U5") (pin "8") (pinfunction "VSSA_8") (pintype "power_in"))
      (node (ref "U6") (pin "1") (pinfunction "GND_1") (pintype "passive"))
      (node (ref "USB1") (pin "1") (pinfunction "SHELL_1") (pintype "passive"))
      (node (ref "USB1") (pin "2") (pinfunction "SHELL_2") (pintype "passive"))
      (node (ref "USB1") (pin "3") (pinfunction "SHELL_3") (pintype "passive"))
      (node (ref "USB1") (pin "4") (pinfunction "SHELL_4") (pintype "passive"))
      (node (ref "USB1") (pin "A1B12") (pinfunction "GND_A1B12") (pintype "passive"))
      (node (ref "USB1") (pin "B1A12") (pinfunction "GND_B1A12") (pintype "passive"))
    )
    (net (code "47") (name "Net-(D1-PadA)") (class "Default")
      (node (ref "D1") (pin "A") (pinfunction "A_A") (pintype "passive"))
      (node (ref "R10") (pin "2") (pinfunction "2_2") (pintype "passive"))
    )
    (net (code "48") (name "Net-(D2-K)") (class "Default")
      (node (ref "D2") (pin "2") (pinfunction "K_2") (pintype "passive"))
      (node (ref "Q2") (pin "3") (pinfunction "C_3") (pintype "passive"))
      (node (ref "R12") (pin "1") (pinfunction "1_1") (pintype "passive"))
    )
    (net (code "49") (name "Net-(M1-EN)") (class "Default")
      (node (ref "M1") (pin "3") (pinfunction "EN_3") (pintype "passive"))
      (node (ref "R5") (pin "2") (pinfunction "2_2") (pintype "passive"))
    )
    (net (code "50") (name "Net-(M1-GPIO0)") (class "Default")
      (node (ref "M1") (pin "18") (pinfunction "GPIO0_18") (pintype "passive"))
      (node (ref "Q1") (pin "2") (pinfunction "E_2") (pintype "passive"))
      (node (ref "R4") (pin "1") (pinfunction "1_1") (pintype "passive"))
      (node (ref "R8") (pin "2") (pinfunction "2_2") (pintype "passive"))
    )
    (net (code "51") (name "Net-(M1-GPIO15)") (class "Default")
      (node (ref "M1") (pin "16") (pinfunction "GPIO15_16") (pintype "passive"))
      (node (ref "R6") (pin "1") (pinfunction "1_1") (pintype "passive"))
    )
    (net (code "52") (name "Net-(M1-RST)") (class "Default")
      (node (ref "M1") (pin "1") (pinfunction "RST_1") (pintype "passive"))
      (node (ref "R2") (pin "2") (pinfunction "2_2") (pintype "passive"))
    )
    (net (code "53") (name "Net-(OLED1-C1N)") (class "Default")
      (node (ref "C15") (pin "1") (pinfunction "1_1") (pintype "passive"))
      (node (ref "OLED1") (pin "4") (pinfunction "C1N_4") (pintype "passive"))
    )
    (net (code "54") (name "Net-(OLED1-C1P)") (class "Default")
      (node (ref "C15") (pin "2") (pinfunction "2_2") (pintype "passive"))
      (node (ref "OLED1") (pin "3") (pinfunction "C1P_3") (pintype "passive"))
    )
    (net (code "55") (name "Net-(OLED1-C2N)") (class "Default")
      (node (ref "C16") (pin "1") (pinfunction "1_1") (pintype "passive"))
      (node (ref "OLED1") (pin "2") (pinfunction "C2N_2") (pintype "passive"))
    )
    (net (code "56") (name "Net-(OLED1-C2P)") (class "Default")
      (node (ref "C16") (pin "2") (pinfunction "2_2") (pintype "passive"))
      (node (ref "OLED1") (pin "1") (pinfunction "C2P_1") (pintype "passive"))
    )
    (net (code "57") (name "Net-(OLED1-IREF)") (class "Default")
      (node (ref "OLED1") (pin "12") (pinfunction "IREF_12") (pintype "passive"))
      (node (ref "R20") (pin "1") (pinfunction "1_1") (pintype "passive"))
    )
    (net (code "58") (name "Net-(OLED1-RES#)") (class "Default")
      (node (ref "C14") (pin "2") (pinfunction "2_2") (pintype "passive"))
      (node (ref "OLED1") (pin "9") (pinfunction "RES#_9") (pintype "passive"))
      (node (ref "R18") (pin "1") (pinfunction "1_1") (pintype "passive"))
    )
    (net (code "59") (name "Net-(OLED1-VCC)") (class "Default")
      (node (ref "C10") (pin "1") (pinfunction "1_1") (pintype "passive"))
      (node (ref "C11") (pin "1") (pinfunction "1_1") (pintype "passive"))
      (node (ref "OLED1") (pin "14") (pinfunction "VCC_14") (pintype "passive"))
    )
    (net (code "60") (name "Net-(OLED1-VCOMH)") (class "Default")
      (node (ref "C13") (pin "2") (pinfunction "2_2") (pintype "passive"))
      (node (ref "OLED1") (pin "13") (pinfunction "VCOMH_13") (pintype "passive"))
    )
    (net (code "61") (name "Net-(Q1-B)") (class "Default")
      (node (ref "Q1") (pin "1") (pinfunction "B_1") (pintype "passive"))
      (node (ref "R7") (pin "1") (pinfunction "1_1") (pintype "passive"))
    )
    (net (code "62") (name "Net-(Q2-B)") (class "Default")
      (node (ref "Q2") (pin "1") (pinfunction "B_1") (pintype "passive"))
      (node (ref "R17") (pin "2") (pinfunction "2_2") (pintype "passive"))
    )
    (net (code "63") (name "Net-(Q2-E)") (class "Default")
      (node (ref "Q2") (pin "2") (pinfunction "E_2") (pintype "passive"))
      (node (ref "R16") (pin "1") (pinfunction "1_1") (pintype "passive"))
      (node (ref "U6") (pin "14") (pinfunction "RTS#_14") (pintype "passive"))
    )
    (net (code "64") (name "Net-(Q3-B)") (class "Default")
      (node (ref "Q3") (pin "1") (pinfunction "B_1") (pintype "passive"))
      (node (ref "R16") (pin "2") (pinfunction "2_2") (pintype "passive"))
    )
    (net (code "65") (name "Net-(Q3-C)") (class "Default")
      (node (ref "Q3") (pin "3") (pinfunction "C_3") (pintype "passive"))
      (node (ref "R19") (pin "2") (pinfunction "2_2") (pintype "passive"))
    )
    (net (code "66") (name "Net-(U2-AD0)") (class "Default")
      (node (ref "R9") (pin "1") (pinfunction "1_1") (pintype "passive"))
      (node (ref "U2") (pin "9") (pinfunction "AD0_9") (pintype "passive"))
    )
    (net (code "67") (name "Net-(U2-CPOUT)") (class "Default")
      (node (ref "C1") (pin "1") (pinfunction "1_1") (pintype "passive"))
      (node (ref "U2") (pin "20") (pinfunction "CPOUT_20") (pintype "passive"))
    )
    (net (code "68") (name "Net-(U2-REGOUT)") (class "Default")
      (node (ref "C9") (pin "2") (pinfunction "2_2") (pintype "passive"))
      (node (ref "U2") (pin "10") (pinfunction "REGOUT_10") (pintype "passive"))
    )
    (net (code "69") (name "Net-(U5A-PD0-OSC_IN)") (class "Default")
      (node (ref "C17") (pin "2") (pinfunction "2_2") (pintype "passive"))
      (node (ref "U5") (pin "5") (pinfunction "PD0-OSC_IN_5") (pintype "bidirectional"))
      (node (ref "X1") (pin "1") (pinfunction "OSC1_1") (pintype "passive"))
    )
    (net (code "70") (name "Net-(U5A-PD1-OSC_OUT)") (class "Default")
      (node (ref "C18") (pin "2") (pinfunction "2_2") (pintype "passive"))
      (node (ref "U5") (pin "6") (pinfunction "PD1-OSC_OUT_6") (pintype "bidirectional"))
      (node (ref "X1") (pin "3") (pinfunction "OSC2_3") (pintype "passive"))
    )
    (net (code "71") (name "Net-(U6-DTR#)") (class "Default")
      (node (ref "R17") (pin "1") (pinfunction "1_1") (pintype "passive"))
      (node (ref "U6") (pin "13") (pinfunction "DTR#_13") (pintype "passive"))
    )
    (net (code "72") (name "Net-(U6-V3.3)") (class "Default")
      (node (ref "C12") (pin "1") (pinfunction "1_1") (pintype "passive"))
      (node (ref "U6") (pin "4") (pinfunction "V3.3_4") (pintype "passive"))
    )
    (net (code "73") (name "Net-(USB1-CC1)") (class "Default")
      (node (ref "R22") (pin "2") (pinfunction "2_2") (pintype "passive"))
      (node (ref "USB1") (pin "A5") (pinfunction "CC1_A5") (pintype "passive"))
    )
    (net (code "74") (name "Net-(USB1-CC2)") (class "Default")
      (node (ref "R23") (pin "2") (pinfunction "2_2") (pintype "passive"))
      (node (ref "USB1") (pin "B5") (pinfunction "CC2_B5") (pintype "passive"))
    )
    (net (code "75") (name "VBUS") (class "Default")
      (node (ref "F1") (pin "1") (pinfunction "1_1") (pintype "passive"))
      (node (ref "USB1") (pin "A4B9") (pinfunction "VBUS_A4B9") (pintype "passive"))
      (node (ref "USB1") (pin "B4A9") (pinfunction "VBUS_B4A9") (pintype "passive"))
    )
    (net (code "76") (name "unconnected-(M1-ADC-Pad2)") (class "Default")
      (node (ref "M1") (pin "2") (pinfunction "ADC_2") (pintype "passive+no_connect"))
    )
    (net (code "77") (name "unconnected-(M1-CS0-Pad9)") (class "Default")
      (node (ref "M1") (pin "9") (pinfunction "CS0_9") (pintype "passive"))
    )
    (net (code "78") (name "unconnected-(M1-GPIO2-Pad17)") (class "Default")
      (node (ref "M1") (pin "17") (pinfunction "GPIO2_17") (pintype "passive+no_connect"))
    )
    (net (code "79") (name "unconnected-(M1-GPIO4-Pad19)") (class "Default")
      (node (ref "M1") (pin "19") (pinfunction "GPIO4_19") (pintype "passive+no_connect"))
    )
    (net (code "80") (name "unconnected-(M1-GPIO5-Pad20)") (class "Default")
      (node (ref "M1") (pin "20") (pinfunction "GPIO5_20") (pintype "passive+no_connect"))
    )
    (net (code "81") (name "unconnected-(M1-GPIO9-Pad11)") (class "Default")
      (node (ref "M1") (pin "11") (pinfunction "GPIO9_11") (pintype "passive"))
    )
    (net (code "82") (name "unconnected-(M1-GPIO10-Pad12)") (class "Default")
      (node (ref "M1") (pin "12") (pinfunction "GPIO10_12") (pintype "passive"))
    )
    (net (code "83") (name "unconnected-(M1-GPIO12-Pad6)") (class "Default")
      (node (ref "M1") (pin "6") (pinfunction "GPIO12_6") (pintype "passive+no_connect"))
    )
    (net (code "84") (name "unconnected-(M1-GPIO13-Pad7)") (class "Default")
      (node (ref "M1") (pin "7") (pinfunction "GPIO13_7") (pintype "passive+no_connect"))
    )
    (net (code "85") (name "unconnected-(M1-GPIO14-Pad5)") (class "Default")
      (node (ref "M1") (pin "5") (pinfunction "GPIO14_5") (pintype "passive+no_connect"))
    )
    (net (code "86") (name "unconnected-(M1-GPIO16-Pad4)") (class "Default")
      (node (ref "M1") (pin "4") (pinfunction "GPIO16_4") (pintype "passive+no_connect"))
    )
    (net (code "87") (name "unconnected-(M1-MISO-Pad10)") (class "Default")
      (node (ref "M1") (pin "10") (pinfunction "MISO_10") (pintype "passive"))
    )
    (net (code "88") (name "unconnected-(M1-MOSI-Pad13)") (class "Default")
      (node (ref "M1") (pin "13") (pinfunction "MOSI_13") (pintype "passive"))
    )
    (net (code "89") (name "unconnected-(M1-SCLK-Pad14)") (class "Default")
      (node (ref "M1") (pin "14") (pinfunction "SCLK_14") (pintype "passive"))
    )
    (net (code "90") (name "unconnected-(M1-VCC-Pad8)") (class "Default")
      (node (ref "M1") (pin "8") (pinfunction "VCC_8") (pintype "passive+no_connect"))
    )
    (net (code "91") (name "unconnected-(OLED1-VBREF-Pad6)") (class "Default")
      (node (ref "OLED1") (pin "6") (pinfunction "VBREF_6") (pintype "passive+no_connect"))
    )
    (net (code "92") (name "unconnected-(U2-AUX_CL-Pad7)") (class "Default")
      (node (ref "U2") (pin "7") (pinfunction "AUX_CL_7") (pintype "passive+no_connect"))
    )
    (net (code "93") (name "unconnected-(U2-AUX_DA-Pad6)") (class "Default")
      (node (ref "U2") (pin "6") (pinfunction "AUX_DA_6") (pintype "passive+no_connect"))
    )
    (net (code "94") (name "unconnected-(U2-NC-Pad2)") (class "Default")
      (node (ref "U2") (pin "2") (pinfunction "NC_2") (pintype "passive+no_connect"))
    )
    (net (code "95") (name "unconnected-(U2-NC-Pad3)") (class "Default")
      (node (ref "U2") (pin "3") (pinfunction "NC_3") (pintype "passive+no_connect"))
    )
    (net (code "96") (name "unconnected-(U2-NC-Pad4)") (class "Default")
      (node (ref "U2") (pin "4") (pinfunction "NC_4") (pintype "passive+no_connect"))
    )
    (net (code "97") (name "unconnected-(U2-NC-Pad5)") (class "Default")
      (node (ref "U2") (pin "5") (pinfunction "NC_5") (pintype "passive+no_connect"))
    )
    (net (code "98") (name "unconnected-(U2-NC-Pad14)") (class "Default")
      (node (ref "U2") (pin "14") (pinfunction "NC_14") (pintype "passive"))
    )
    (net (code "99") (name "unconnected-(U2-NC-Pad16)") (class "Default")
      (node (ref "U2") (pin "16") (pinfunction "NC_16") (pintype "passive+no_connect"))
    )
    (net (code "100") (name "unconnected-(U2-RESV-Pad19)") (class "Default")
      (node (ref "U2") (pin "19") (pinfunction "RESV_19") (pintype "passive+no_connect"))
    )
    (net (code "101") (name "unconnected-(U2-RESV-Pad21)") (class "Default")
      (node (ref "U2") (pin "21") (pinfunction "RESV_21") (pintype "passive+no_connect"))
    )
    (net (code "102") (name "unconnected-(U2-RESV-Pad22)") (class "Default")
      (node (ref "U2") (pin "22") (pinfunction "RESV_22") (pintype "passive+no_connect"))
    )
    (net (code "103") (name "unconnected-(U3-Output-Pad4)") (class "Default")
      (node (ref "U3") (pin "4") (pinfunction "Output_4") (pintype "passive+no_connect"))
    )
    (net (code "104") (name "unconnected-(U4-SPLIT-Pad5)") (class "Default")
      (node (ref "U4") (pin "5") (pinfunction "SPLIT_5") (pintype "passive"))
    )
    (net (code "105") (name "unconnected-(U4-STB-Pad8)") (class "Default")
      (node (ref "U4") (pin "8") (pinfunction "STB_8") (pintype "passive"))
    )
    (net (code "106") (name "unconnected-(U6-CTS#-Pad9)") (class "Default")
      (node (ref "U6") (pin "9") (pinfunction "CTS#_9") (pintype "passive"))
    )
    (net (code "107") (name "unconnected-(U6-DCD#-Pad12)") (class "Default")
      (node (ref "U6") (pin "12") (pinfunction "DCD#_12") (pintype "passive"))
    )
    (net (code "108") (name "unconnected-(U6-DSR#-Pad10)") (class "Default")
      (node (ref "U6") (pin "10") (pinfunction "DSR#_10") (pintype "passive"))
    )
    (net (code "109") (name "unconnected-(U6-R232-Pad15)") (class "Default")
      (node (ref "U6") (pin "15") (pinfunction "R232_15") (pintype "passive"))
    )
    (net (code "110") (name "unconnected-(U6-RI#-Pad11)") (class "Default")
      (node (ref "U6") (pin "11") (pinfunction "RI#_11") (pintype "passive"))
    )
    (net (code "111") (name "unconnected-(U6-XI-Pad7)") (class "Default")
      (node (ref "U6") (pin "7") (pinfunction "XI_7") (pintype "passive"))
    )
    (net (code "112") (name "unconnected-(U6-XO-Pad8)") (class "Default")
      (node (ref "U6") (pin "8") (pinfunction "XO_8") (pintype "passive"))
    )
    (net (code "113") (name "unconnected-(USB1-SBU1-PadA8)") (class "Default")
      (node (ref "USB1") (pin "A8") (pinfunction "SBU1_A8") (pintype "passive"))
    )
    (net (code "114") (name "unconnected-(USB1-SBU2-PadB8)") (class "Default")
      (node (ref "USB1") (pin "B8") (pinfunction "SBU2_B8") (pintype "passive"))
    )
    (net (code "115") (name "unconnected-(X1-GND-Pad2)") (class "Default")
      (node (ref "X1") (pin "2") (pinfunction "GND_2") (pintype "passive+no_connect"))
    )
    (net (code "116") (name "unconnected-(X1-GND-Pad4)") (class "Default")
      (node (ref "X1") (pin "4") (pinfunction "GND_4") (pintype "passive+no_connect"))
    )
  )
)
